# satellites_pcb_th_v1.net
KiCad netlist of a schematic drawn in EAGLE
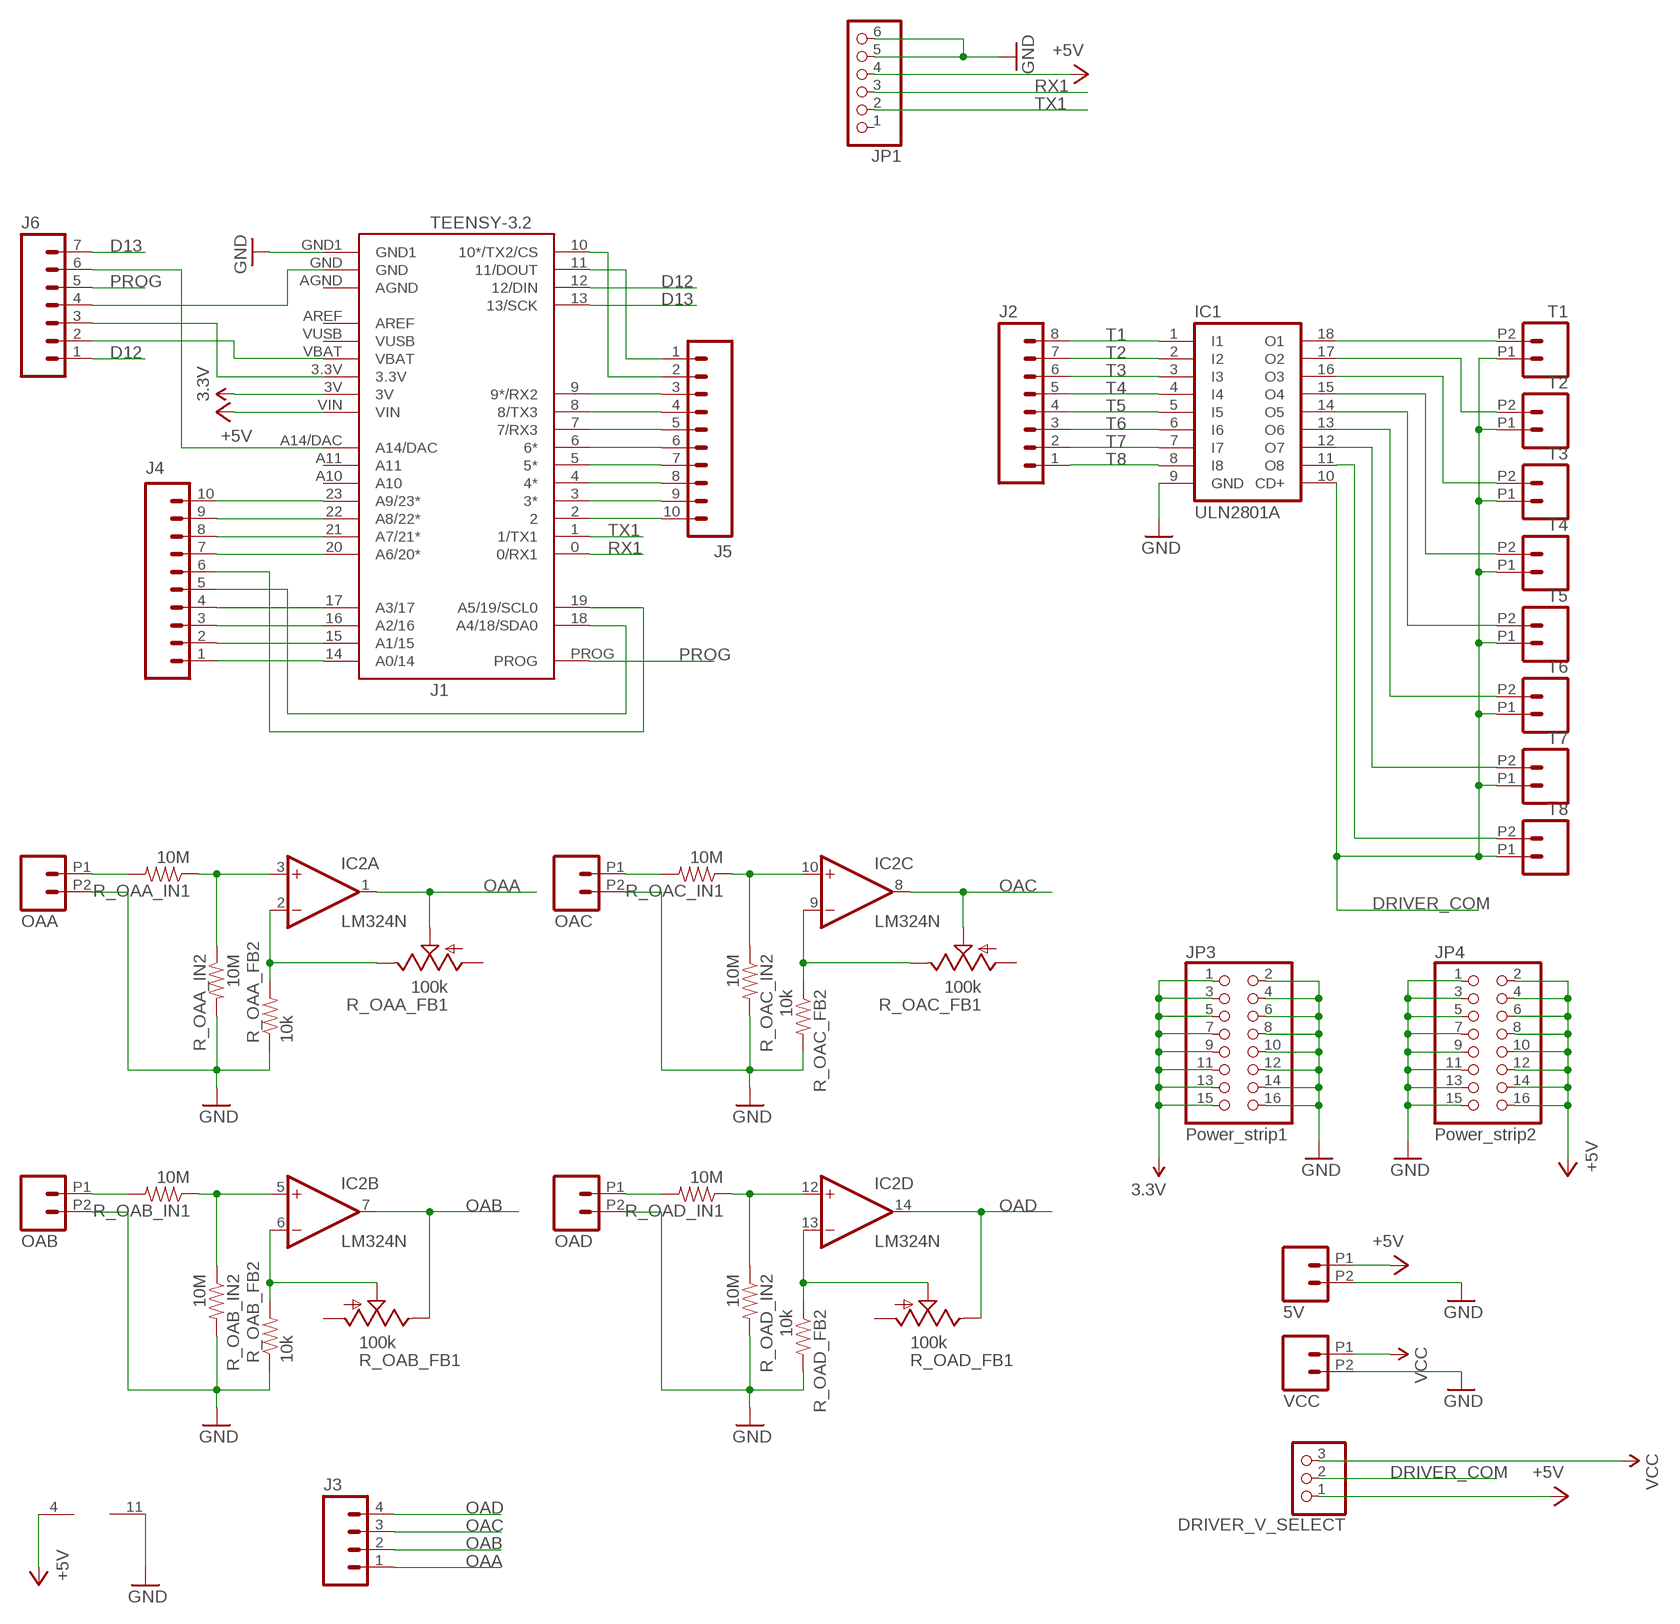
[diagram p0: schematic, sheet 1]

(export (version "E")
  (design (tool "Eeschema 10.0.6"))
  (components
    (comp (ref "5V")
      (value "M022.54MM_SCREWTERM")
      (footprint "eagle-import:1X02_2.54_SCREWTERM")
      (libsource (lib "eagle-import") (part "M022.54MM_SCREWTERM"))
    )
    (comp (ref "DRIVER_V_SELECT")
      (value "PINHD-1X3")
      (footprint "eagle-import:1X03")
      (libsource (lib "eagle-import") (part "PINHD-1X3"))
    )
    (comp (ref "IC1")
      (value "ULN2801A")
      (footprint "eagle-import:DIL18")
      (libsource (lib "eagle-import") (part "ULN2801A"))
    )
    (comp (ref "IC2")
      (value "LM324N")
      (footprint "eagle-import:DIL14")
      (libsource (lib "eagle-import") (part "LM324N"))
    )
    (comp (ref "J1")
      (value "TEENSY-3.2")
      (footprint "eagle-import:TEENSY-3.1_NOSILK")
      (libsource (lib "eagle-import") (part "TEENSY-3.1NOSILK"))
    )
    (comp (ref "J2")
      (value "M08")
      (footprint "eagle-import:1X08_ROUND")
      (libsource (lib "eagle-import") (part "M08"))
    )
    (comp (ref "J3")
      (value "M04PTH")
      (footprint "eagle-import:1X04")
      (libsource (lib "eagle-import") (part "M04PTH"))
    )
    (comp (ref "J4")
      (value "M10NO_SILK_PTH_FEMALE")
      (footprint "eagle-import:1X10_NO_SILK")
      (libsource (lib "eagle-import") (part "M10NO_SILK_PTH_FEMALE"))
    )
    (comp (ref "J5")
      (value "M10NO_SILK_PTH_FEMALE")
      (footprint "eagle-import:1X10_NO_SILK")
      (libsource (lib "eagle-import") (part "M10NO_SILK_PTH_FEMALE"))
    )
    (comp (ref "J6")
      (value "M07")
      (footprint "eagle-import:1X07")
      (libsource (lib "eagle-import") (part "M07"))
    )
    (comp (ref "JP1")
      (value "PINHD-1X6")
      (footprint "eagle-import:1X06")
      (libsource (lib "eagle-import") (part "PINHD-1X6"))
    )
    (comp (ref "JP3")
      (value "Power_strip1")
      (footprint "eagle-import:2X08")
      (libsource (lib "eagle-import") (part "PINHD-2X8"))
    )
    (comp (ref "JP4")
      (value "Power_strip2")
      (footprint "eagle-import:2X08")
      (libsource (lib "eagle-import") (part "PINHD-2X8"))
    )
    (comp (ref "OAA")
      (value "M022.54MM_SCREWTERM")
      (footprint "eagle-import:1X02_2.54_SCREWTERM")
      (libsource (lib "eagle-import") (part "M022.54MM_SCREWTERM"))
    )
    (comp (ref "OAB")
      (value "M022.54MM_SCREWTERM")
      (footprint "eagle-import:1X02_2.54_SCREWTERM")
      (libsource (lib "eagle-import") (part "M022.54MM_SCREWTERM"))
    )
    (comp (ref "OAC")
      (value "M022.54MM_SCREWTERM")
      (footprint "eagle-import:1X02_2.54_SCREWTERM")
      (libsource (lib "eagle-import") (part "M022.54MM_SCREWTERM"))
    )
    (comp (ref "OAD")
      (value "M022.54MM_SCREWTERM")
      (footprint "eagle-import:1X02_2.54_SCREWTERM")
      (libsource (lib "eagle-import") (part "M022.54MM_SCREWTERM"))
    )
    (comp (ref "R_OAA_FB1")
      (value "100k")
      (footprint "eagle-import:B64W")
      (libsource (lib "eagle-import") (part "TRIM_US-B64W"))
    )
    (comp (ref "R_OAA_FB2")
      (value "10k")
      (footprint "eagle-import:AXIAL-0.3")
      (libsource (lib "eagle-import") (part "RESISTORAXIAL-0.3"))
    )
    (comp (ref "R_OAA_IN1")
      (value "10M")
      (footprint "eagle-import:AXIAL-0.3")
      (libsource (lib "eagle-import") (part "RESISTORAXIAL-0.3"))
    )
    (comp (ref "R_OAA_IN2")
      (value "10M")
      (footprint "eagle-import:AXIAL-0.3")
      (libsource (lib "eagle-import") (part "RESISTORAXIAL-0.3"))
    )
    (comp (ref "R_OAB_FB1")
      (value "100k")
      (footprint "eagle-import:B64W")
      (libsource (lib "eagle-import") (part "TRIM_US-B64W"))
    )
    (comp (ref "R_OAB_FB2")
      (value "10k")
      (footprint "eagle-import:AXIAL-0.3")
      (libsource (lib "eagle-import") (part "RESISTORAXIAL-0.3"))
    )
    (comp (ref "R_OAB_IN1")
      (value "10M")
      (footprint "eagle-import:AXIAL-0.3")
      (libsource (lib "eagle-import") (part "RESISTORAXIAL-0.3"))
    )
    (comp (ref "R_OAB_IN2")
      (value "10M")
      (footprint "eagle-import:AXIAL-0.3")
      (libsource (lib "eagle-import") (part "RESISTORAXIAL-0.3"))
    )
    (comp (ref "R_OAC_FB1")
      (value "100k")
      (footprint "eagle-import:B64W")
      (libsource (lib "eagle-import") (part "TRIM_US-B64W"))
    )
    (comp (ref "R_OAC_FB2")
      (value "10k")
      (footprint "eagle-import:AXIAL-0.3")
      (libsource (lib "eagle-import") (part "RESISTORAXIAL-0.3"))
    )
    (comp (ref "R_OAC_IN1")
      (value "10M")
      (footprint "eagle-import:AXIAL-0.3")
      (libsource (lib "eagle-import") (part "RESISTORAXIAL-0.3"))
    )
    (comp (ref "R_OAC_IN2")
      (value "10M")
      (footprint "eagle-import:AXIAL-0.3")
      (libsource (lib "eagle-import") (part "RESISTORAXIAL-0.3"))
    )
    (comp (ref "R_OAD_FB1")
      (value "100k")
      (footprint "eagle-import:B64W")
      (libsource (lib "eagle-import") (part "TRIM_US-B64W"))
    )
    (comp (ref "R_OAD_FB2")
      (value "10k")
      (footprint "eagle-import:AXIAL-0.3")
      (libsource (lib "eagle-import") (part "RESISTORAXIAL-0.3"))
    )
    (comp (ref "R_OAD_IN1")
      (value "10M")
      (footprint "eagle-import:AXIAL-0.3")
      (libsource (lib "eagle-import") (part "RESISTORAXIAL-0.3"))
    )
    (comp (ref "R_OAD_IN2")
      (value "10M")
      (footprint "eagle-import:AXIAL-0.3")
      (libsource (lib "eagle-import") (part "RESISTORAXIAL-0.3"))
    )
    (comp (ref "T1")
      (value "M022.54MM_SCREWTERM")
      (footprint "eagle-import:1X02_2.54_SCREWTERM")
      (libsource (lib "eagle-import") (part "M022.54MM_SCREWTERM"))
    )
    (comp (ref "T2")
      (value "M022.54MM_SCREWTERM")
      (footprint "eagle-import:1X02_2.54_SCREWTERM")
      (libsource (lib "eagle-import") (part "M022.54MM_SCREWTERM"))
    )
    (comp (ref "T3")
      (value "M022.54MM_SCREWTERM")
      (footprint "eagle-import:1X02_2.54_SCREWTERM")
      (libsource (lib "eagle-import") (part "M022.54MM_SCREWTERM"))
    )
    (comp (ref "T4")
      (value "M022.54MM_SCREWTERM")
      (footprint "eagle-import:1X02_2.54_SCREWTERM")
      (libsource (lib "eagle-import") (part "M022.54MM_SCREWTERM"))
    )
    (comp (ref "T5")
      (value "M022.54MM_SCREWTERM")
      (footprint "eagle-import:1X02_2.54_SCREWTERM")
      (libsource (lib "eagle-import") (part "M022.54MM_SCREWTERM"))
    )
    (comp (ref "T6")
      (value "M022.54MM_SCREWTERM")
      (footprint "eagle-import:1X02_2.54_SCREWTERM")
      (libsource (lib "eagle-import") (part "M022.54MM_SCREWTERM"))
    )
    (comp (ref "T7")
      (value "M022.54MM_SCREWTERM")
      (footprint "eagle-import:1X02_2.54_SCREWTERM")
      (libsource (lib "eagle-import") (part "M022.54MM_SCREWTERM"))
    )
    (comp (ref "T8")
      (value "M022.54MM_SCREWTERM")
      (footprint "eagle-import:1X02_2.54_SCREWTERM")
      (libsource (lib "eagle-import") (part "M022.54MM_SCREWTERM"))
    )
    (comp (ref "VCC")
      (value "M022.54MM_SCREWTERM")
      (footprint "eagle-import:1X02_2.54_SCREWTERM")
      (libsource (lib "eagle-import") (part "M022.54MM_SCREWTERM"))
    )
  )
  (nets
    (net (code "1") (name "+5V") (class "Default")
      (node (ref "5V") (pin "P1") (pinfunction "1_P1") (pintype "passive"))
      (node (ref "DRIVER_V_SELECT") (pin "1") (pinfunction "1_1") (pintype "passive"))
      (node (ref "IC2") (pin "4") (pinfunction "V+_4") (pintype "power_in"))
      (node (ref "J1") (pin "VIN") (pinfunction "VIN_VIN") (pintype "bidirectional"))
      (node (ref "JP1") (pin "4") (pinfunction "4_4") (pintype "passive"))
      (node (ref "JP4") (pin "10") (pinfunction "10_10") (pintype "passive"))
      (node (ref "JP4") (pin "12") (pinfunction "12_12") (pintype "passive"))
      (node (ref "JP4") (pin "14") (pinfunction "14_14") (pintype "passive"))
      (node (ref "JP4") (pin "16") (pinfunction "16_16") (pintype "passive"))
      (node (ref "JP4") (pin "2") (pinfunction "2_2") (pintype "passive"))
      (node (ref "JP4") (pin "4") (pinfunction "4_4") (pintype "passive"))
      (node (ref "JP4") (pin "6") (pinfunction "6_6") (pintype "passive"))
      (node (ref "JP4") (pin "8") (pinfunction "8_8") (pintype "passive"))
    )
    (net (code "2") (name "/D12") (class "Default")
      (node (ref "J1") (pin "12") (pinfunction "12/DIN_12") (pintype "bidirectional"))
      (node (ref "J6") (pin "1") (pinfunction "1_1") (pintype "passive"))
    )
    (net (code "3") (name "/D13") (class "Default")
      (node (ref "J1") (pin "13") (pinfunction "13/SCK_13") (pintype "bidirectional"))
      (node (ref "J6") (pin "7") (pinfunction "7_7") (pintype "passive"))
    )
    (net (code "4") (name "/DRIVER_COM") (class "Default")
      (node (ref "DRIVER_V_SELECT") (pin "2") (pinfunction "2_2") (pintype "passive"))
      (node (ref "IC1") (pin "10") (pinfunction "CD+_10") (pintype "passive"))
      (node (ref "T1") (pin "P1") (pinfunction "1_P1") (pintype "passive"))
      (node (ref "T2") (pin "P1") (pinfunction "1_P1") (pintype "passive"))
      (node (ref "T3") (pin "P1") (pinfunction "1_P1") (pintype "passive"))
      (node (ref "T4") (pin "P1") (pinfunction "1_P1") (pintype "passive"))
      (node (ref "T5") (pin "P1") (pinfunction "1_P1") (pintype "passive"))
      (node (ref "T6") (pin "P1") (pinfunction "1_P1") (pintype "passive"))
      (node (ref "T7") (pin "P1") (pinfunction "1_P1") (pintype "passive"))
      (node (ref "T8") (pin "P1") (pinfunction "1_P1") (pintype "passive"))
    )
    (net (code "5") (name "/OAA") (class "Default")
      (node (ref "IC2") (pin "1") (pinfunction "OUT_1") (pintype "output"))
      (node (ref "J3") (pin "1") (pinfunction "1_1") (pintype "passive"))
      (node (ref "R_OAA_FB1") (pin "S") (pinfunction "S_S") (pintype "passive"))
    )
    (net (code "6") (name "/OAB") (class "Default")
      (node (ref "IC2") (pin "7") (pinfunction "OUT_7") (pintype "output"))
      (node (ref "J3") (pin "2") (pinfunction "2_2") (pintype "passive"))
      (node (ref "R_OAB_FB1") (pin "E") (pinfunction "E_E") (pintype "passive"))
    )
    (net (code "7") (name "/OAC") (class "Default")
      (node (ref "IC2") (pin "8") (pinfunction "OUT_8") (pintype "output"))
      (node (ref "J3") (pin "3") (pinfunction "3_3") (pintype "passive"))
      (node (ref "R_OAC_FB1") (pin "S") (pinfunction "S_S") (pintype "passive"))
    )
    (net (code "8") (name "/OAD") (class "Default")
      (node (ref "IC2") (pin "14") (pinfunction "OUT_14") (pintype "output"))
      (node (ref "J3") (pin "4") (pinfunction "4_4") (pintype "passive"))
      (node (ref "R_OAD_FB1") (pin "E") (pinfunction "E_E") (pintype "passive"))
    )
    (net (code "9") (name "/PROG") (class "Default")
      (node (ref "J1") (pin "PROG") (pinfunction "PROG_PROG") (pintype "bidirectional"))
      (node (ref "J6") (pin "5") (pinfunction "5_5") (pintype "passive"))
    )
    (net (code "10") (name "/RX1") (class "Default")
      (node (ref "J1") (pin "0") (pinfunction "0/RX1_0") (pintype "bidirectional"))
      (node (ref "JP1") (pin "3") (pinfunction "3_3") (pintype "passive"))
    )
    (net (code "11") (name "/T1") (class "Default")
      (node (ref "IC1") (pin "1") (pinfunction "I1_1") (pintype "input"))
      (node (ref "J2") (pin "8") (pinfunction "8_8") (pintype "passive"))
    )
    (net (code "12") (name "/T2") (class "Default")
      (node (ref "IC1") (pin "2") (pinfunction "I2_2") (pintype "input"))
      (node (ref "J2") (pin "7") (pinfunction "7_7") (pintype "passive"))
    )
    (net (code "13") (name "/T3") (class "Default")
      (node (ref "IC1") (pin "3") (pinfunction "I3_3") (pintype "input"))
      (node (ref "J2") (pin "6") (pinfunction "6_6") (pintype "passive"))
    )
    (net (code "14") (name "/T4") (class "Default")
      (node (ref "IC1") (pin "4") (pinfunction "I4_4") (pintype "input"))
      (node (ref "J2") (pin "5") (pinfunction "5_5") (pintype "passive"))
    )
    (net (code "15") (name "/T5") (class "Default")
      (node (ref "IC1") (pin "5") (pinfunction "I5_5") (pintype "input"))
      (node (ref "J2") (pin "4") (pinfunction "4_4") (pintype "passive"))
    )
    (net (code "16") (name "/T6") (class "Default")
      (node (ref "IC1") (pin "6") (pinfunction "I6_6") (pintype "input"))
      (node (ref "J2") (pin "3") (pinfunction "3_3") (pintype "passive"))
    )
    (net (code "17") (name "/T7") (class "Default")
      (node (ref "IC1") (pin "7") (pinfunction "I7_7") (pintype "input"))
      (node (ref "J2") (pin "2") (pinfunction "2_2") (pintype "passive"))
    )
    (net (code "18") (name "/T8") (class "Default")
      (node (ref "IC1") (pin "8") (pinfunction "I8_8") (pintype "input"))
      (node (ref "J2") (pin "1") (pinfunction "1_1") (pintype "passive"))
    )
    (net (code "19") (name "/TX1") (class "Default")
      (node (ref "J1") (pin "1") (pinfunction "1/TX1_1") (pintype "bidirectional"))
      (node (ref "JP1") (pin "2") (pinfunction "2_2") (pintype "passive"))
    )
    (net (code "20") (name "3.3V") (class "Default")
      (node (ref "J1") (pin "3V") (pinfunction "3V_3V") (pintype "bidirectional"))
      (node (ref "JP3") (pin "1") (pinfunction "1_1") (pintype "passive"))
      (node (ref "JP3") (pin "11") (pinfunction "11_11") (pintype "passive"))
      (node (ref "JP3") (pin "13") (pinfunction "13_13") (pintype "passive"))
      (node (ref "JP3") (pin "15") (pinfunction "15_15") (pintype "passive"))
      (node (ref "JP3") (pin "3") (pinfunction "3_3") (pintype "passive"))
      (node (ref "JP3") (pin "5") (pinfunction "5_5") (pintype "passive"))
      (node (ref "JP3") (pin "7") (pinfunction "7_7") (pintype "passive"))
      (node (ref "JP3") (pin "9") (pinfunction "9_9") (pintype "passive"))
    )
    (net (code "21") (name "GND") (class "Default")
      (node (ref "5V") (pin "P2") (pinfunction "2_P2") (pintype "passive"))
      (node (ref "IC1") (pin "9") (pinfunction "GND_9") (pintype "power_in"))
      (node (ref "IC2") (pin "11") (pinfunction "V-_11") (pintype "power_in"))
      (node (ref "J1") (pin "GND1") (pinfunction "GND1_GND1") (pintype "bidirectional"))
      (node (ref "JP1") (pin "5") (pinfunction "5_5") (pintype "passive"))
      (node (ref "JP1") (pin "6") (pinfunction "6_6") (pintype "passive"))
      (node (ref "JP3") (pin "10") (pinfunction "10_10") (pintype "passive"))
      (node (ref "JP3") (pin "12") (pinfunction "12_12") (pintype "passive"))
      (node (ref "JP3") (pin "14") (pinfunction "14_14") (pintype "passive"))
      (node (ref "JP3") (pin "16") (pinfunction "16_16") (pintype "passive"))
      (node (ref "JP3") (pin "2") (pinfunction "2_2") (pintype "passive"))
      (node (ref "JP3") (pin "4") (pinfunction "4_4") (pintype "passive"))
      (node (ref "JP3") (pin "6") (pinfunction "6_6") (pintype "passive"))
      (node (ref "JP3") (pin "8") (pinfunction "8_8") (pintype "passive"))
      (node (ref "JP4") (pin "1") (pinfunction "1_1") (pintype "passive"))
      (node (ref "JP4") (pin "11") (pinfunction "11_11") (pintype "passive"))
      (node (ref "JP4") (pin "13") (pinfunction "13_13") (pintype "passive"))
      (node (ref "JP4") (pin "15") (pinfunction "15_15") (pintype "passive"))
      (node (ref "JP4") (pin "3") (pinfunction "3_3") (pintype "passive"))
      (node (ref "JP4") (pin "5") (pinfunction "5_5") (pintype "passive"))
      (node (ref "JP4") (pin "7") (pinfunction "7_7") (pintype "passive"))
      (node (ref "JP4") (pin "9") (pinfunction "9_9") (pintype "passive"))
      (node (ref "OAA") (pin "P2") (pinfunction "2_P2") (pintype "passive"))
      (node (ref "OAB") (pin "P2") (pinfunction "2_P2") (pintype "passive"))
      (node (ref "OAC") (pin "P2") (pinfunction "2_P2") (pintype "passive"))
      (node (ref "OAD") (pin "P2") (pinfunction "2_P2") (pintype "passive"))
      (node (ref "R_OAA_FB2") (pin "P$1") (pinfunction "1_P$1") (pintype "passive"))
      (node (ref "R_OAA_IN2") (pin "P$2") (pinfunction "2_P$2") (pintype "passive"))
      (node (ref "R_OAB_FB2") (pin "P$1") (pinfunction "1_P$1") (pintype "passive"))
      (node (ref "R_OAB_IN2") (pin "P$2") (pinfunction "2_P$2") (pintype "passive"))
      (node (ref "R_OAC_FB2") (pin "P$2") (pinfunction "2_P$2") (pintype "passive"))
      (node (ref "R_OAC_IN2") (pin "P$2") (pinfunction "2_P$2") (pintype "passive"))
      (node (ref "R_OAD_FB2") (pin "P$2") (pinfunction "2_P$2") (pintype "passive"))
      (node (ref "R_OAD_IN2") (pin "P$2") (pinfunction "2_P$2") (pintype "passive"))
      (node (ref "VCC") (pin "P2") (pinfunction "2_P2") (pintype "passive"))
    )
    (net (code "22") (name "Net-(IC1-O1)") (class "Default")
      (node (ref "IC1") (pin "18") (pinfunction "O1_18") (pintype "open_collector"))
      (node (ref "T1") (pin "P2") (pinfunction "2_P2") (pintype "passive"))
    )
    (net (code "23") (name "Net-(IC1-O2)") (class "Default")
      (node (ref "IC1") (pin "17") (pinfunction "O2_17") (pintype "open_collector"))
      (node (ref "T2") (pin "P2") (pinfunction "2_P2") (pintype "passive"))
    )
    (net (code "24") (name "Net-(IC1-O3)") (class "Default")
      (node (ref "IC1") (pin "16") (pinfunction "O3_16") (pintype "open_collector"))
      (node (ref "T3") (pin "P2") (pinfunction "2_P2") (pintype "passive"))
    )
    (net (code "25") (name "Net-(IC1-O4)") (class "Default")
      (node (ref "IC1") (pin "15") (pinfunction "O4_15") (pintype "open_collector"))
      (node (ref "T4") (pin "P2") (pinfunction "2_P2") (pintype "passive"))
    )
    (net (code "26") (name "Net-(IC1-O5)") (class "Default")
      (node (ref "IC1") (pin "14") (pinfunction "O5_14") (pintype "open_collector"))
      (node (ref "T5") (pin "P2") (pinfunction "2_P2") (pintype "passive"))
    )
    (net (code "27") (name "Net-(IC1-O6)") (class "Default")
      (node (ref "IC1") (pin "13") (pinfunction "O6_13") (pintype "open_collector"))
      (node (ref "T6") (pin "P2") (pinfunction "2_P2") (pintype "passive"))
    )
    (net (code "28") (name "Net-(IC1-O7)") (class "Default")
      (node (ref "IC1") (pin "12") (pinfunction "O7_12") (pintype "open_collector"))
      (node (ref "T7") (pin "P2") (pinfunction "2_P2") (pintype "passive"))
    )
    (net (code "29") (name "Net-(IC1-O8)") (class "Default")
      (node (ref "IC1") (pin "11") (pinfunction "O8_11") (pintype "open_collector"))
      (node (ref "T8") (pin "P2") (pinfunction "2_P2") (pintype "passive"))
    )
    (net (code "30") (name "Net-(IC2A-+IN)") (class "Default")
      (node (ref "IC2") (pin "3") (pinfunction "+IN_3") (pintype "input"))
      (node (ref "R_OAA_IN1") (pin "P$1") (pinfunction "1_P$1") (pintype "passive"))
      (node (ref "R_OAA_IN2") (pin "P$1") (pinfunction "1_P$1") (pintype "passive"))
    )
    (net (code "31") (name "Net-(IC2A--IN)") (class "Default")
      (node (ref "IC2") (pin "2") (pinfunction "-IN_2") (pintype "input"))
      (node (ref "R_OAA_FB1") (pin "E") (pinfunction "E_E") (pintype "passive"))
      (node (ref "R_OAA_FB2") (pin "P$2") (pinfunction "2_P$2") (pintype "passive"))
    )
    (net (code "32") (name "Net-(IC2B-+IN)") (class "Default")
      (node (ref "IC2") (pin "5") (pinfunction "+IN_5") (pintype "input"))
      (node (ref "R_OAB_IN1") (pin "P$1") (pinfunction "1_P$1") (pintype "passive"))
      (node (ref "R_OAB_IN2") (pin "P$1") (pinfunction "1_P$1") (pintype "passive"))
    )
    (net (code "33") (name "Net-(IC2B--IN)") (class "Default")
      (node (ref "IC2") (pin "6") (pinfunction "-IN_6") (pintype "input"))
      (node (ref "R_OAB_FB1") (pin "S") (pinfunction "S_S") (pintype "passive"))
      (node (ref "R_OAB_FB2") (pin "P$2") (pinfunction "2_P$2") (pintype "passive"))
    )
    (net (code "34") (name "Net-(IC2C-+IN)") (class "Default")
      (node (ref "IC2") (pin "10") (pinfunction "+IN_10") (pintype "input"))
      (node (ref "R_OAC_IN1") (pin "P$1") (pinfunction "1_P$1") (pintype "passive"))
      (node (ref "R_OAC_IN2") (pin "P$1") (pinfunction "1_P$1") (pintype "passive"))
    )
    (net (code "35") (name "Net-(IC2C--IN)") (class "Default")
      (node (ref "IC2") (pin "9") (pinfunction "-IN_9") (pintype "input"))
      (node (ref "R_OAC_FB1") (pin "E") (pinfunction "E_E") (pintype "passive"))
      (node (ref "R_OAC_FB2") (pin "P$1") (pinfunction "1_P$1") (pintype "passive"))
    )
    (net (code "36") (name "Net-(IC2D-+IN)") (class "Default")
      (node (ref "IC2") (pin "12") (pinfunction "+IN_12") (pintype "input"))
      (node (ref "R_OAD_IN1") (pin "P$1") (pinfunction "1_P$1") (pintype "passive"))
      (node (ref "R_OAD_IN2") (pin "P$1") (pinfunction "1_P$1") (pintype "passive"))
    )
    (net (code "37") (name "Net-(IC2D--IN)") (class "Default")
      (node (ref "IC2") (pin "13") (pinfunction "-IN_13") (pintype "input"))
      (node (ref "R_OAD_FB1") (pin "S") (pinfunction "S_S") (pintype "passive"))
      (node (ref "R_OAD_FB2") (pin "P$1") (pinfunction "1_P$1") (pintype "passive"))
    )
    (net (code "38") (name "Net-(J1-3*)") (class "Default")
      (node (ref "J1") (pin "3") (pinfunction "3*_3") (pintype "bidirectional"))
      (node (ref "J5") (pin "9") (pinfunction "9_9") (pintype "passive"))
    )
    (net (code "39") (name "Net-(J1-4*)") (class "Default")
      (node (ref "J1") (pin "4") (pinfunction "4*_4") (pintype "bidirectional"))
      (node (ref "J5") (pin "8") (pinfunction "8_8") (pintype "passive"))
    )
    (net (code "40") (name "Net-(J1-5*)") (class "Default")
      (node (ref "J1") (pin "5") (pinfunction "5*_5") (pintype "bidirectional"))
      (node (ref "J5") (pin "7") (pinfunction "7_7") (pintype "passive"))
    )
    (net (code "41") (name "Net-(J1-6*)") (class "Default")
      (node (ref "J1") (pin "6") (pinfunction "6*_6") (pintype "bidirectional"))
      (node (ref "J5") (pin "6") (pinfunction "6_6") (pintype "passive"))
    )
    (net (code "42") (name "Net-(J1-7{slash}RX3)") (class "Default")
      (node (ref "J1") (pin "7") (pinfunction "7/RX3_7") (pintype "bidirectional"))
      (node (ref "J5") (pin "5") (pinfunction "5_5") (pintype "passive"))
    )
    (net (code "43") (name "Net-(J1-8{slash}TX3)") (class "Default")
      (node (ref "J1") (pin "8") (pinfunction "8/TX3_8") (pintype "bidirectional"))
      (node (ref "J5") (pin "4") (pinfunction "4_4") (pintype "passive"))
    )
    (net (code "44") (name "Net-(J1-9*{slash}RX2)") (class "Default")
      (node (ref "J1") (pin "9") (pinfunction "9*/RX2_9") (pintype "bidirectional"))
      (node (ref "J5") (pin "3") (pinfunction "3_3") (pintype "passive"))
    )
    (net (code "45") (name "Net-(J1-10*{slash}TX2{slash}CS)") (class "Default")
      (node (ref "J1") (pin "10") (pinfunction "10*/TX2/CS_10") (pintype "bidirectional"))
      (node (ref "J5") (pin "2") (pinfunction "2_2") (pintype "passive"))
    )
    (net (code "46") (name "Net-(J1-11{slash}DOUT)") (class "Default")
      (node (ref "J1") (pin "11") (pinfunction "11/DOUT_11") (pintype "bidirectional"))
      (node (ref "J5") (pin "1") (pinfunction "1_1") (pintype "passive"))
    )
    (net (code "47") (name "Net-(J1-A0{slash}14)") (class "Default")
      (node (ref "J1") (pin "14") (pinfunction "A0/14_14") (pintype "bidirectional"))
      (node (ref "J4") (pin "1") (pinfunction "1_1") (pintype "passive"))
    )
    (net (code "48") (name "Net-(J1-A1{slash}15)") (class "Default")
      (node (ref "J1") (pin "15") (pinfunction "A1/15_15") (pintype "bidirectional"))
      (node (ref "J4") (pin "2") (pinfunction "2_2") (pintype "passive"))
    )
    (net (code "49") (name "Net-(J1-A2{slash}16)") (class "Default")
      (node (ref "J1") (pin "16") (pinfunction "A2/16_16") (pintype "bidirectional"))
      (node (ref "J4") (pin "3") (pinfunction "3_3") (pintype "passive"))
    )
    (net (code "50") (name "Net-(J1-A3{slash}17)") (class "Default")
      (node (ref "J1") (pin "17") (pinfunction "A3/17_17") (pintype "bidirectional"))
      (node (ref "J4") (pin "4") (pinfunction "4_4") (pintype "passive"))
    )
    (net (code "51") (name "Net-(J1-A4{slash}18{slash}SDA0)") (class "Default")
      (node (ref "J1") (pin "18") (pinfunction "A4/18/SDA0_18") (pintype "bidirectional"))
      (node (ref "J4") (pin "5") (pinfunction "5_5") (pintype "passive"))
    )
    (net (code "52") (name "Net-(J1-A5{slash}19{slash}SCL0)") (class "Default")
      (node (ref "J1") (pin "19") (pinfunction "A5/19/SCL0_19") (pintype "bidirectional"))
      (node (ref "J4") (pin "6") (pinfunction "6_6") (pintype "passive"))
    )
    (net (code "53") (name "Net-(J1-A6{slash}20*)") (class "Default")
      (node (ref "J1") (pin "20") (pinfunction "A6/20*_20") (pintype "bidirectional"))
      (node (ref "J4") (pin "7") (pinfunction "7_7") (pintype "passive"))
    )
    (net (code "54") (name "Net-(J1-A7{slash}21*)") (class "Default")
      (node (ref "J1") (pin "21") (pinfunction "A7/21*_21") (pintype "bidirectional"))
      (node (ref "J4") (pin "8") (pinfunction "8_8") (pintype "passive"))
    )
    (net (code "55") (name "Net-(J1-A8{slash}22*)") (class "Default")
      (node (ref "J1") (pin "22") (pinfunction "A8/22*_22") (pintype "bidirectional"))
      (node (ref "J4") (pin "9") (pinfunction "9_9") (pintype "passive"))
    )
    (net (code "56") (name "Net-(J1-A9{slash}23*)") (class "Default")
      (node (ref "J1") (pin "23") (pinfunction "A9/23*_23") (pintype "bidirectional"))
      (node (ref "J4") (pin "10") (pinfunction "10_10") (pintype "passive"))
    )
    (net (code "57") (name "Net-(J1-Pad2)") (class "Default")
      (node (ref "J1") (pin "2") (pinfunction "2_2") (pintype "bidirectional"))
      (node (ref "J5") (pin "10") (pinfunction "10_10") (pintype "passive"))
    )
    (net (code "58") (name "Net-(J1-Pad3.3V)") (class "Default")
      (node (ref "J1") (pin "3.3V") (pinfunction "3.3V_3.3V") (pintype "bidirectional"))
      (node (ref "J6") (pin "3") (pinfunction "3_3") (pintype "passive"))
    )
    (net (code "59") (name "Net-(J1-PadA14{slash}DAC)") (class "Default")
      (node (ref "J1") (pin "A14/DAC") (pinfunction "A14/DAC_A14/DAC") (pintype "bidirectional"))
      (node (ref "J6") (pin "6") (pinfunction "6_6") (pintype "passive"))
    )
    (net (code "60") (name "Net-(J1-PadGND)") (class "Default")
      (node (ref "J1") (pin "GND") (pinfunction "GND_GND") (pintype "bidirectional"))
      (node (ref "J6") (pin "4") (pinfunction "4_4") (pintype "passive"))
    )
    (net (code "61") (name "Net-(J1-PadVBAT)") (class "Default")
      (node (ref "J1") (pin "VBAT") (pinfunction "VBAT_VBAT") (pintype "bidirectional"))
      (node (ref "J6") (pin "2") (pinfunction "2_2") (pintype "passive"))
    )
    (net (code "62") (name "Net-(OAA-1)") (class "Default")
      (node (ref "OAA") (pin "P1") (pinfunction "1_P1") (pintype "passive"))
      (node (ref "R_OAA_IN1") (pin "P$2") (pinfunction "2_P$2") (pintype "passive"))
    )
    (net (code "63") (name "Net-(OAB-1)") (class "Default")
      (node (ref "OAB") (pin "P1") (pinfunction "1_P1") (pintype "passive"))
      (node (ref "R_OAB_IN1") (pin "P$2") (pinfunction "2_P$2") (pintype "passive"))
    )
    (net (code "64") (name "Net-(OAC-1)") (class "Default")
      (node (ref "OAC") (pin "P1") (pinfunction "1_P1") (pintype "passive"))
      (node (ref "R_OAC_IN1") (pin "P$2") (pinfunction "2_P$2") (pintype "passive"))
    )
    (net (code "65") (name "Net-(OAD-1)") (class "Default")
      (node (ref "OAD") (pin "P1") (pinfunction "1_P1") (pintype "passive"))
      (node (ref "R_OAD_IN1") (pin "P$2") (pinfunction "2_P$2") (pintype "passive"))
    )
    (net (code "66") (name "VCC") (class "Default")
      (node (ref "DRIVER_V_SELECT") (pin "3") (pinfunction "3_3") (pintype "passive"))
      (node (ref "VCC") (pin "P1") (pinfunction "1_P1") (pintype "passive"))
    )
    (net (code "67") (name "unconnected-(J1-PadA10)") (class "Default")
      (node (ref "J1") (pin "A10") (pinfunction "A10_A10") (pintype "bidirectional"))
    )
    (net (code "68") (name "unconnected-(J1-PadA11)") (class "Default")
      (node (ref "J1") (pin "A11") (pinfunction "A11_A11") (pintype "bidirectional"))
    )
    (net (code "69") (name "unconnected-(J1-PadAGND)") (class "Default")
      (node (ref "J1") (pin "AGND") (pinfunction "AGND_AGND") (pintype "bidirectional"))
    )
    (net (code "70") (name "unconnected-(J1-PadAREF)") (class "Default")
      (node (ref "J1") (pin "AREF") (pinfunction "AREF_AREF") (pintype "bidirectional"))
    )
    (net (code "71") (name "unconnected-(J1-PadVUSB)") (class "Default")
      (node (ref "J1") (pin "VUSB") (pinfunction "VUSB_VUSB") (pintype "bidirectional"))
    )
    (net (code "72") (name "unconnected-(JP1-Pad1)") (class "Default")
      (node (ref "JP1") (pin "1") (pinfunction "1_1") (pintype "passive"))
    )
    (net (code "73") (name "unconnected-(R_OAA_FB1-PadA)") (class "Default")
      (node (ref "R_OAA_FB1") (pin "A") (pinfunction "A_A") (pintype "passive"))
    )
    (net (code "74") (name "unconnected-(R_OAB_FB1-PadA)") (class "Default")
      (node (ref "R_OAB_FB1") (pin "A") (pinfunction "A_A") (pintype "passive"))
    )
    (net (code "75") (name "unconnected-(R_OAC_FB1-PadA)") (class "Default")
      (node (ref "R_OAC_FB1") (pin "A") (pinfunction "A_A") (pintype "passive"))
    )
    (net (code "76") (name "unconnected-(R_OAD_FB1-PadA)") (class "Default")
      (node (ref "R_OAD_FB1") (pin "A") (pinfunction "A_A") (pintype "passive"))
    )
  )
)
